# DICO_v100.net
KiCad netlist of a schematic drawn in EAGLE
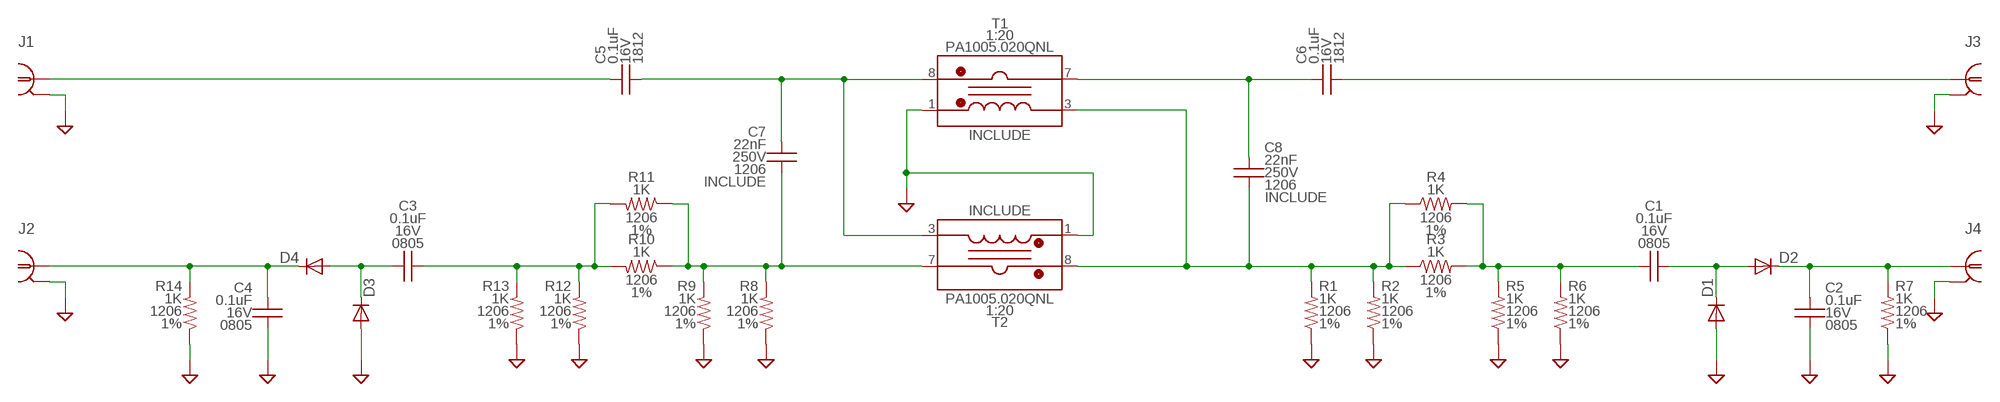
[diagram p0: schematic, sheet 1]

(export (version "E")
  (design (tool "Eeschema 10.0.6"))
  (components
    (comp (ref "C1")
      (value "0.1uF")
      (footprint "eagle-import:0805_IPC-7351B")
      (fields (field (name "PACKAGE") "0805") (field (name "VOLTAGE") "16V"))
      (libsource (lib "eagle-import") (part "C0805_IPCC-0.1U-16V-0805-X7R"))
    )
    (comp (ref "C2")
      (value "0.1uF")
      (footprint "eagle-import:0805_IPC-7351B")
      (fields (field (name "VOLTAGE") "16V"))
      (libsource (lib "eagle-import") (part "C0805_IPCC-0.1U-16V-0805-X7R"))
    )
    (comp (ref "C3")
      (value "0.1uF")
      (footprint "eagle-import:0805_IPC-7351B")
      (fields (field (name "PACKAGE") "0805") (field (name "VOLTAGE") "16V"))
      (libsource (lib "eagle-import") (part "C0805_IPCC-0.1U-16V-0805-X7R"))
    )
    (comp (ref "C4")
      (value "0.1uF")
      (footprint "eagle-import:0805_IPC-7351B")
      (fields (field (name "VOLTAGE") "16V"))
      (libsource (lib "eagle-import") (part "C0805_IPCC-0.1U-16V-0805-X7R"))
    )
    (comp (ref "C5")
      (value "0.1uF")
      (footprint "eagle-import:C1812")
      (fields (field (name "VOLTAGE") "16V"))
      (libsource (lib "eagle-import") (part "CC1812"))
    )
    (comp (ref "C6")
      (value "0.1uF")
      (footprint "eagle-import:C1812")
      (fields (field (name "VOLTAGE") "16V"))
      (libsource (lib "eagle-import") (part "CC1812"))
    )
    (comp (ref "C7")
      (value "22nF")
      (footprint "eagle-import:C1206")
      (fields (field (name "PARTNO") "C3216NP02E223J160AA") (field (name "VOLTAGE") "250V"))
      (libsource (lib "eagle-import") (part "CC1206C-22N-250V-5%-1206-NP0"))
    )
    (comp (ref "C8")
      (value "22nF")
      (footprint "eagle-import:C1206")
      (fields (field (name "PARTNO") "C3216NP02E223J160AA") (field (name "VOLTAGE") "250V"))
      (libsource (lib "eagle-import") (part "CC1206C-22N-250V-5%-1206-NP0"))
    )
    (comp (ref "D1")
      (value "DIODE-SOD123")
      (footprint "eagle-import:SOD123")
      (libsource (lib "eagle-import") (part "DIODE-SOD123"))
    )
    (comp (ref "D2")
      (value "DIODE-SOD123")
      (footprint "eagle-import:SOD123")
      (libsource (lib "eagle-import") (part "DIODE-SOD123"))
    )
    (comp (ref "D3")
      (value "DIODE-SOD123")
      (footprint "eagle-import:SOD123")
      (libsource (lib "eagle-import") (part "DIODE-SOD123"))
    )
    (comp (ref "D4")
      (value "DIODE-SOD123")
      (footprint "eagle-import:SOD123")
      (libsource (lib "eagle-import") (part "DIODE-SOD123"))
    )
    (comp (ref "J1")
      (value "COAXBNC_EDGE")
      (footprint "eagle-import:BNC_EDGE")
      (libsource (lib "eagle-import") (part "COAXBNC_EDGE"))
    )
    (comp (ref "J2")
      (value "COAXBNC_EDGE")
      (footprint "eagle-import:BNC_EDGE")
      (libsource (lib "eagle-import") (part "COAXBNC_EDGE"))
    )
    (comp (ref "J3")
      (value "COAXBNC_EDGE")
      (footprint "eagle-import:BNC_EDGE")
      (libsource (lib "eagle-import") (part "COAXBNC_EDGE"))
    )
    (comp (ref "J4")
      (value "COAXBNC_EDGE")
      (footprint "eagle-import:BNC_EDGE")
      (libsource (lib "eagle-import") (part "COAXBNC_EDGE"))
    )
    (comp (ref "R1")
      (value "1K")
      (footprint "eagle-import:R1206")
      (fields (field (name "POWER") "0.25"))
      (libsource (lib "eagle-import") (part "RR1206R-1.0K-1%-1206-0.25W"))
    )
    (comp (ref "R2")
      (value "1K")
      (footprint "eagle-import:R1206")
      (fields (field (name "POWER") "0.25"))
      (libsource (lib "eagle-import") (part "RR1206R-1.0K-1%-1206-0.25W"))
    )
    (comp (ref "R3")
      (value "1K")
      (footprint "eagle-import:R1206")
      (fields (field (name "POWER") "0.25"))
      (libsource (lib "eagle-import") (part "R90R1206R-1.0K-1%-1206-0.25W"))
    )
    (comp (ref "R4")
      (value "1K")
      (footprint "eagle-import:R1206")
      (fields (field (name "POWER") "0.25"))
      (libsource (lib "eagle-import") (part "R90R1206R-1.0K-1%-1206-0.25W"))
    )
    (comp (ref "R5")
      (value "1K")
      (footprint "eagle-import:R1206")
      (fields (field (name "POWER") "0.25"))
      (libsource (lib "eagle-import") (part "RR1206R-1.0K-1%-1206-0.25W"))
    )
    (comp (ref "R6")
      (value "1K")
      (footprint "eagle-import:R1206")
      (fields (field (name "POWER") "0.25"))
      (libsource (lib "eagle-import") (part "RR1206R-1.0K-1%-1206-0.25W"))
    )
    (comp (ref "R7")
      (value "1K")
      (footprint "eagle-import:R1206")
      (fields (field (name "POWER") "0.25"))
      (libsource (lib "eagle-import") (part "RR1206R-1.0K-1%-1206-0.25W"))
    )
    (comp (ref "R8")
      (value "1K")
      (footprint "eagle-import:R1206")
      (fields (field (name "POWER") "0.25"))
      (libsource (lib "eagle-import") (part "RR1206R-1.0K-1%-1206-0.25W"))
    )
    (comp (ref "R9")
      (value "1K")
      (footprint "eagle-import:R1206")
      (fields (field (name "POWER") "0.25"))
      (libsource (lib "eagle-import") (part "RR1206R-1.0K-1%-1206-0.25W"))
    )
    (comp (ref "R10")
      (value "1K")
      (footprint "eagle-import:R1206")
      (fields (field (name "POWER") "0.25"))
      (libsource (lib "eagle-import") (part "R90R1206R-1.0K-1%-1206-0.25W"))
    )
    (comp (ref "R11")
      (value "1K")
      (footprint "eagle-import:R1206")
      (fields (field (name "POWER") "0.25"))
      (libsource (lib "eagle-import") (part "R90R1206R-1.0K-1%-1206-0.25W"))
    )
    (comp (ref "R12")
      (value "1K")
      (footprint "eagle-import:R1206")
      (fields (field (name "POWER") "0.25"))
      (libsource (lib "eagle-import") (part "RR1206R-1.0K-1%-1206-0.25W"))
    )
    (comp (ref "R13")
      (value "1K")
      (footprint "eagle-import:R1206")
      (fields (field (name "POWER") "0.25"))
      (libsource (lib "eagle-import") (part "RR1206R-1.0K-1%-1206-0.25W"))
    )
    (comp (ref "R14")
      (value "1K")
      (footprint "eagle-import:R1206")
      (fields (field (name "POWER") "0.25"))
      (libsource (lib "eagle-import") (part "RR1206R-1.0K-1%-1206-0.25W"))
    )
    (comp (ref "T1")
      (value "TRAFO_CURRENTSENSEPA1005.020QNLPA1005")
      (footprint "eagle-import:PA1005")
      (fields (field (name "PARTNO") "PA1005.020QNL"))
      (libsource (lib "eagle-import") (part "TRAFO_CURRENTSENSEPA1005PA1005.020QNL"))
    )
    (comp (ref "T2")
      (value "TRAFO_CURRENTSENSEPA1005.020QNLPA1005")
      (footprint "eagle-import:PA1005")
      (fields (field (name "PARTNO") "PA1005.020QNL"))
      (libsource (lib "eagle-import") (part "TRAFO_CURRENTSENSEPA1005PA1005.020QNL"))
    )
  )
  (nets
    (net (code "1") (name "GND") (class "Default")
      (node (ref "C2") (pin "2") (pinfunction "2_2") (pintype "passive"))
      (node (ref "C4") (pin "2") (pinfunction "2_2") (pintype "passive"))
      (node (ref "D1") (pin "A") (pinfunction "A_A") (pintype "passive"))
      (node (ref "D3") (pin "A") (pinfunction "A_A") (pintype "passive"))
      (node (ref "J1") (pin "G1") (pinfunction "GND1_G1") (pintype "power_in"))
      (node (ref "J1") (pin "G2") (pinfunction "GND1_G2") (pintype "power_in"))
      (node (ref "J1") (pin "G3") (pinfunction "GND1_G3") (pintype "power_in"))
      (node (ref "J1") (pin "G4") (pinfunction "GND1_G4") (pintype "power_in"))
      (node (ref "J2") (pin "G1") (pinfunction "GND1_G1") (pintype "power_in"))
      (node (ref "J2") (pin "G2") (pinfunction "GND1_G2") (pintype "power_in"))
      (node (ref "J2") (pin "G3") (pinfunction "GND1_G3") (pintype "power_in"))
      (node (ref "J2") (pin "G4") (pinfunction "GND1_G4") (pintype "power_in"))
      (node (ref "J3") (pin "G1") (pinfunction "GND1_G1") (pintype "power_in"))
      (node (ref "J3") (pin "G2") (pinfunction "GND1_G2") (pintype "power_in"))
      (node (ref "J3") (pin "G3") (pinfunction "GND1_G3") (pintype "power_in"))
      (node (ref "J3") (pin "G4") (pinfunction "GND1_G4") (pintype "power_in"))
      (node (ref "J4") (pin "G1") (pinfunction "GND1_G1") (pintype "power_in"))
      (node (ref "J4") (pin "G2") (pinfunction "GND1_G2") (pintype "power_in"))
      (node (ref "J4") (pin "G3") (pinfunction "GND1_G3") (pintype "power_in"))
      (node (ref "J4") (pin "G4") (pinfunction "GND1_G4") (pintype "power_in"))
      (node (ref "R1") (pin "2") (pinfunction "2_2") (pintype "passive"))
      (node (ref "R12") (pin "2") (pinfunction "2_2") (pintype "passive"))
      (node (ref "R13") (pin "2") (pinfunction "2_2") (pintype "passive"))
      (node (ref "R14") (pin "2") (pinfunction "2_2") (pintype "passive"))
      (node (ref "R2") (pin "2") (pinfunction "2_2") (pintype "passive"))
      (node (ref "R5") (pin "2") (pinfunction "2_2") (pintype "passive"))
      (node (ref "R6") (pin "2") (pinfunction "2_2") (pintype "passive"))
      (node (ref "R7") (pin "2") (pinfunction "2_2") (pintype "passive"))
      (node (ref "R8") (pin "2") (pinfunction "2_2") (pintype "passive"))
      (node (ref "R9") (pin "2") (pinfunction "2_2") (pintype "passive"))
      (node (ref "T1") (pin "1") (pinfunction "SS_1") (pintype "passive"))
      (node (ref "T2") (pin "1") (pinfunction "SS_1") (pintype "passive"))
    )
    (net (code "2") (name "Net-(C1-Pad1)") (class "Default")
      (node (ref "C1") (pin "1") (pinfunction "1_1") (pintype "passive"))
      (node (ref "R3") (pin "2") (pinfunction "2_2") (pintype "passive"))
      (node (ref "R4") (pin "2") (pinfunction "2_2") (pintype "passive"))
      (node (ref "R5") (pin "1") (pinfunction "1_1") (pintype "passive"))
      (node (ref "R6") (pin "1") (pinfunction "1_1") (pintype "passive"))
    )
    (net (code "3") (name "Net-(C1-Pad2)") (class "Default")
      (node (ref "C1") (pin "2") (pinfunction "2_2") (pintype "passive"))
      (node (ref "D1") (pin "C") (pinfunction "C_C") (pintype "passive"))
      (node (ref "D2") (pin "A") (pinfunction "A_A") (pintype "passive"))
    )
    (net (code "4") (name "Net-(C3-Pad1)") (class "Default")
      (node (ref "C3") (pin "1") (pinfunction "1_1") (pintype "passive"))
      (node (ref "R10") (pin "2") (pinfunction "2_2") (pintype "passive"))
      (node (ref "R11") (pin "2") (pinfunction "2_2") (pintype "passive"))
      (node (ref "R12") (pin "1") (pinfunction "1_1") (pintype "passive"))
      (node (ref "R13") (pin "1") (pinfunction "1_1") (pintype "passive"))
    )
    (net (code "5") (name "Net-(C3-Pad2)") (class "Default")
      (node (ref "C3") (pin "2") (pinfunction "2_2") (pintype "passive"))
      (node (ref "D3") (pin "C") (pinfunction "C_C") (pintype "passive"))
      (node (ref "D4") (pin "A") (pinfunction "A_A") (pintype "passive"))
    )
    (net (code "6") (name "Net-(J1-1)") (class "Default")
      (node (ref "C5") (pin "1") (pinfunction "1_1") (pintype "passive"))
      (node (ref "J1") (pin "C") (pinfunction "1_C") (pintype "passive"))
    )
    (net (code "7") (name "Net-(J2-1)") (class "Default")
      (node (ref "C4") (pin "1") (pinfunction "1_1") (pintype "passive"))
      (node (ref "D4") (pin "C") (pinfunction "C_C") (pintype "passive"))
      (node (ref "J2") (pin "C") (pinfunction "1_C") (pintype "passive"))
      (node (ref "R14") (pin "1") (pinfunction "1_1") (pintype "passive"))
    )
    (net (code "8") (name "Net-(J3-1)") (class "Default")
      (node (ref "C6") (pin "2") (pinfunction "2_2") (pintype "passive"))
      (node (ref "J3") (pin "C") (pinfunction "1_C") (pintype "passive"))
    )
    (net (code "9") (name "Net-(J4-1)") (class "Default")
      (node (ref "C2") (pin "1") (pinfunction "1_1") (pintype "passive"))
      (node (ref "D2") (pin "C") (pinfunction "C_C") (pintype "passive"))
      (node (ref "J4") (pin "C") (pinfunction "1_C") (pintype "passive"))
      (node (ref "R7") (pin "1") (pinfunction "1_1") (pintype "passive"))
    )
    (net (code "10") (name "Net-(T1-PF)") (class "Default")
      (node (ref "C6") (pin "1") (pinfunction "1_1") (pintype "passive"))
      (node (ref "C8") (pin "1") (pinfunction "1_1") (pintype "passive"))
      (node (ref "T1") (pin "7") (pinfunction "PF_7") (pintype "passive"))
    )
    (net (code "11") (name "Net-(T1-PS)") (class "Default")
      (node (ref "C5") (pin "2") (pinfunction "2_2") (pintype "passive"))
      (node (ref "C7") (pin "1") (pinfunction "1_1") (pintype "passive"))
      (node (ref "T1") (pin "8") (pinfunction "PS_8") (pintype "passive"))
      (node (ref "T2") (pin "3") (pinfunction "SF_3") (pintype "passive"))
    )
    (net (code "12") (name "Net-(T1-SF)") (class "Default")
      (node (ref "C8") (pin "2") (pinfunction "2_2") (pintype "passive"))
      (node (ref "R1") (pin "1") (pinfunction "1_1") (pintype "passive"))
      (node (ref "R2") (pin "1") (pinfunction "1_1") (pintype "passive"))
      (node (ref "R3") (pin "1") (pinfunction "1_1") (pintype "passive"))
      (node (ref "R4") (pin "1") (pinfunction "1_1") (pintype "passive"))
      (node (ref "T1") (pin "3") (pinfunction "SF_3") (pintype "passive"))
      (node (ref "T2") (pin "8") (pinfunction "PS_8") (pintype "passive"))
    )
    (net (code "13") (name "Net-(T2-PF)") (class "Default")
      (node (ref "C7") (pin "2") (pinfunction "2_2") (pintype "passive"))
      (node (ref "R10") (pin "1") (pinfunction "1_1") (pintype "passive"))
      (node (ref "R11") (pin "1") (pinfunction "1_1") (pintype "passive"))
      (node (ref "R8") (pin "1") (pinfunction "1_1") (pintype "passive"))
      (node (ref "R9") (pin "1") (pinfunction "1_1") (pintype "passive"))
      (node (ref "T2") (pin "7") (pinfunction "PF_7") (pintype "passive"))
    )
  )
)
